# 12-sdcard.net
KiCad netlist of a schematic drawn in Altium Designer
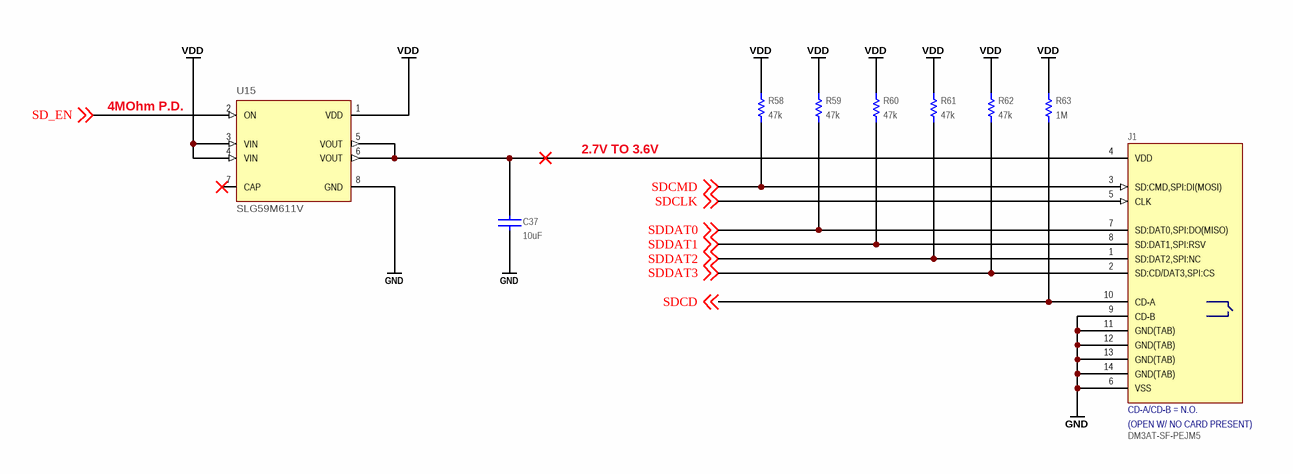
[diagram p0: 12-sdcard.SchDoc]

(export (version "E")
  (design (tool "Eeschema 10.0.6"))
  (components
    (comp (ref "C37")
      (value "10uF")
      (footprint "CAPC160X80X90L20N")
      (description "Ceramic Capacitor 10uF ±20% 25V X5R 0603")
      (fields (field (name "MANUFACTURER") "Murata") (field (name "VOLTAGE") "25V"))
      (libsource (lib "generic") (part "CAP 0603"))
    )
    (comp (ref "J1")
      (value "DM3AT-SF-PEJM5")
      (footprint "DM3AT-SF-PEJM5")
      (description "Micro SD Card Connector, R/A")
      (fields (field (name "MANUFACTURER") "Hirose"))
      (libsource (lib "hirose") (part "DM3AT-SF-PEJM5"))
    )
    (comp (ref "R58")
      (value "47k")
      (footprint "RESC2012X70N")
      (description "Thick Film Resistor 47k ±1% 0805")
      (fields (field (name "MANUFACTURER") "Panasonic") (field (name "TOLERANCE") "±1%"))
      (libsource (lib "Graviton") (part "RES 0402"))
    )
    (comp (ref "R59")
      (value "47k")
      (footprint "RESC2012X70N")
      (description "Thick Film Resistor 47k ±1% 0805")
      (fields (field (name "MANUFACTURER") "Panasonic") (field (name "TOLERANCE") "±1%"))
      (libsource (lib "Graviton") (part "RES 0402"))
    )
    (comp (ref "R60")
      (value "47k")
      (footprint "RESC2012X70N")
      (description "Thick Film Resistor 47k ±1% 0805")
      (fields (field (name "MANUFACTURER") "Panasonic") (field (name "TOLERANCE") "±1%"))
      (libsource (lib "Graviton") (part "RES 0402"))
    )
    (comp (ref "R61")
      (value "47k")
      (footprint "RESC2012X70N")
      (description "Thick Film Resistor 47k ±1% 0805")
      (fields (field (name "MANUFACTURER") "Panasonic") (field (name "TOLERANCE") "±1%"))
      (libsource (lib "Graviton") (part "RES 0402"))
    )
    (comp (ref "R62")
      (value "47k")
      (footprint "RESC2012X70N")
      (description "Thick Film Resistor 47k ±1% 0805")
      (fields (field (name "MANUFACTURER") "Panasonic") (field (name "TOLERANCE") "±1%"))
      (libsource (lib "Graviton") (part "RES 0402"))
    )
    (comp (ref "R63")
      (value "1M")
      (footprint "RESC2012X70N")
      (description "Thick Film Resistor 1M ±1% 0805")
      (fields (field (name "MANUFACTURER") "Panasonic") (field (name "TOLERANCE") "±1%"))
      (libsource (lib "Graviton") (part "RES 0402"))
    )
    (comp (ref "U15")
      (value "SLG59M611V")
      (footprint "DFN200X150X80-8N")
      (description "High-Side Load Switch")
      (fields (field (name "MANUFACTURER") "Silego"))
      (libsource (lib "silego") (part "SLG59M611V"))
    )
  )
  (nets
    (net (code "1") (name "GND") (class "Default")
      (node (ref "C37") (pin "1") (pinfunction "1_1") (pintype "passive"))
      (node (ref "J1") (pin "11") (pinfunction "GND(TAB)_11") (pintype "power_in"))
      (node (ref "J1") (pin "12") (pinfunction "GND(TAB)_12") (pintype "power_in"))
      (node (ref "J1") (pin "13") (pinfunction "GND(TAB)_13") (pintype "power_in"))
      (node (ref "J1") (pin "14") (pinfunction "GND(TAB)_14") (pintype "power_in"))
      (node (ref "J1") (pin "6") (pinfunction "VSS_6") (pintype "power_in"))
      (node (ref "J1") (pin "9") (pinfunction "CD-B_9") (pintype "passive"))
      (node (ref "U15") (pin "8") (pinfunction "GND_8") (pintype "power_in"))
    )
    (net (code "2") (name "Net-(J1-VDD)") (class "Default")
      (node (ref "C37") (pin "2") (pinfunction "2_2") (pintype "passive"))
      (node (ref "J1") (pin "4") (pinfunction "VDD_4") (pintype "power_in"))
      (node (ref "U15") (pin "5") (pinfunction "VOUT_5") (pintype "output"))
      (node (ref "U15") (pin "6") (pinfunction "VOUT_6") (pintype "output"))
    )
    (net (code "3") (name "SDCD") (class "Default")
      (node (ref "J1") (pin "10") (pinfunction "CD-A_10") (pintype "power_in"))
      (node (ref "R63") (pin "1") (pinfunction "1_1") (pintype "passive"))
    )
    (net (code "4") (name "SDCLK") (class "Default")
      (node (ref "J1") (pin "5") (pinfunction "CLK_5") (pintype "input"))
    )
    (net (code "5") (name "SDCMD") (class "Default")
      (node (ref "J1") (pin "3") (pinfunction "SD:CMD,SPI:DI(MOSI)_3") (pintype "input"))
      (node (ref "R58") (pin "1") (pinfunction "1_1") (pintype "passive"))
    )
    (net (code "6") (name "SDDAT0") (class "Default")
      (node (ref "J1") (pin "7") (pinfunction "SD:DAT0,SPI:DO(MISO)_7") (pintype "passive"))
      (node (ref "R59") (pin "1") (pinfunction "1_1") (pintype "passive"))
    )
    (net (code "7") (name "SDDAT1") (class "Default")
      (node (ref "J1") (pin "8") (pinfunction "SD:DAT1,SPI:RSV_8") (pintype "passive"))
      (node (ref "R60") (pin "1") (pinfunction "1_1") (pintype "passive"))
    )
    (net (code "8") (name "SDDAT2") (class "Default")
      (node (ref "J1") (pin "1") (pinfunction "SD:DAT2,SPI:NC_1") (pintype "passive"))
      (node (ref "R61") (pin "1") (pinfunction "1_1") (pintype "passive"))
    )
    (net (code "9") (name "SDDAT3") (class "Default")
      (node (ref "J1") (pin "2") (pinfunction "SD:CD/DAT3,SPI:CS_2") (pintype "passive"))
      (node (ref "R62") (pin "1") (pinfunction "1_1") (pintype "passive"))
    )
    (net (code "10") (name "SD_EN") (class "Default")
      (node (ref "U15") (pin "2") (pinfunction "ON_2") (pintype "input"))
    )
    (net (code "11") (name "VDD") (class "Default")
      (node (ref "R58") (pin "2") (pinfunction "2_2") (pintype "passive"))
      (node (ref "R59") (pin "2") (pinfunction "2_2") (pintype "passive"))
      (node (ref "R60") (pin "2") (pinfunction "2_2") (pintype "passive"))
      (node (ref "R61") (pin "2") (pinfunction "2_2") (pintype "passive"))
      (node (ref "R62") (pin "2") (pinfunction "2_2") (pintype "passive"))
      (node (ref "R63") (pin "2") (pinfunction "2_2") (pintype "passive"))
      (node (ref "U15") (pin "1") (pinfunction "VDD_1") (pintype "power_in"))
      (node (ref "U15") (pin "3") (pinfunction "VIN_3") (pintype "input"))
      (node (ref "U15") (pin "4") (pinfunction "VIN_4") (pintype "input"))
    )
    (net (code "12") (name "unconnected-(U15-CAP-Pad7)") (class "Default")
      (node (ref "U15") (pin "7") (pinfunction "CAP_7") (pintype "passive+no_connect"))
    )
  )
)
